# DAC_SET.net
KiCad netlist of a schematic drawn in Altium Designer
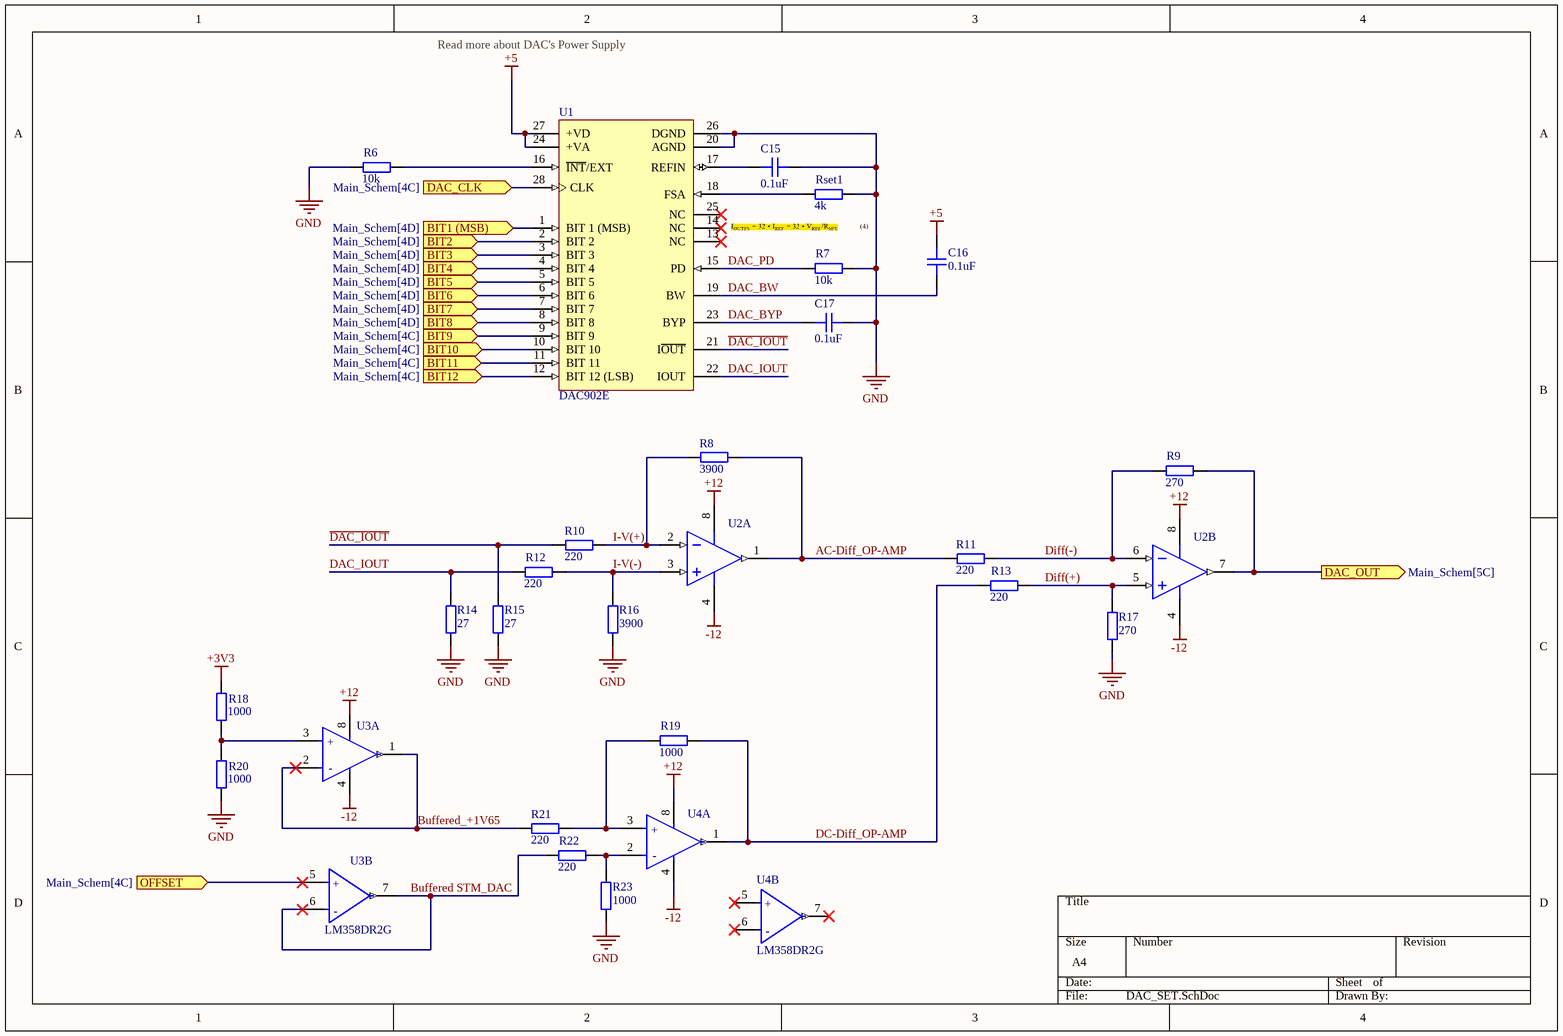
[diagram p0: DAC_SET.SchDoc]

(export (version "E")
  (design (tool "Eeschema 10.0.6"))
  (components
    (comp (ref "C15")
      (value "0.1uF")
      (footprint "CAP_1210")
      (description "Capacitor SMD 1210")
      (libsource (lib "Schematic-Lib-PhilsLab (1)") (part "CAP_1210"))
    )
    (comp (ref "C16")
      (value "0.1uF")
      (footprint "CAP_1210")
      (description "Capacitor SMD 1210")
      (libsource (lib "Schematic-Lib-PhilsLab (1)") (part "CAP_1210"))
    )
    (comp (ref "C17")
      (value "0.1uF")
      (footprint "CAP_1210")
      (description "Capacitor SMD 1210")
      (libsource (lib "Schematic-Lib-PhilsLab (1)") (part "CAP_1210"))
    )
    (comp (ref "R6")
      (value "10k")
      (footprint "RES_0805")
      (description "Resistor SMD 0805")
      (libsource (lib "Schematic-Lib-PhilsLab (1)") (part "RES_0805"))
    )
    (comp (ref "R7")
      (value "10k")
      (footprint "RES_0805")
      (description "Resistor SMD 0805")
      (libsource (lib "Schematic-Lib-PhilsLab (1)") (part "RES_0805"))
    )
    (comp (ref "R8")
      (value "3900")
      (footprint "RES_0805")
      (description "Resistor SMD 0805")
      (libsource (lib "Schematic-Lib-PhilsLab (1)") (part "RES_0805"))
    )
    (comp (ref "R9")
      (value "270")
      (footprint "RES_0805")
      (description "Resistor SMD 0805")
      (libsource (lib "Schematic-Lib-PhilsLab (1)") (part "RES_0805"))
    )
    (comp (ref "R10")
      (value "220")
      (footprint "RES_0805")
      (description "Resistor SMD 0805")
      (libsource (lib "Schematic-Lib-PhilsLab (1)") (part "RES_0805"))
    )
    (comp (ref "R11")
      (value "220")
      (footprint "RES_0805")
      (description "Resistor SMD 0805")
      (libsource (lib "Schematic-Lib-PhilsLab (1)") (part "RES_0805"))
    )
    (comp (ref "R12")
      (value "220")
      (footprint "RES_0805")
      (description "Resistor SMD 0805")
      (libsource (lib "Schematic-Lib-PhilsLab (1)") (part "RES_0805"))
    )
    (comp (ref "R13")
      (value "220")
      (footprint "RES_0805")
      (description "Resistor SMD 0805")
      (libsource (lib "Schematic-Lib-PhilsLab (1)") (part "RES_0805"))
    )
    (comp (ref "R14")
      (value "27")
      (footprint "RES_0805")
      (description "Resistor SMD 0805")
      (libsource (lib "Schematic-Lib-PhilsLab (1)") (part "RES_0805"))
    )
    (comp (ref "R15")
      (value "27")
      (footprint "RES_0805")
      (description "Resistor SMD 0805")
      (libsource (lib "Schematic-Lib-PhilsLab (1)") (part "RES_0805"))
    )
    (comp (ref "R16")
      (value "3900")
      (footprint "RES_0805")
      (description "Resistor SMD 0805")
      (libsource (lib "Schematic-Lib-PhilsLab (1)") (part "RES_0805"))
    )
    (comp (ref "R17")
      (value "270")
      (footprint "RES_0805")
      (description "Resistor SMD 0805")
      (libsource (lib "Schematic-Lib-PhilsLab (1)") (part "RES_0805"))
    )
    (comp (ref "R18")
      (value "1000")
      (footprint "RES_0805")
      (description "Resistor SMD 0805")
      (libsource (lib "Schematic-Lib-PhilsLab (1)") (part "RES_0805"))
    )
    (comp (ref "R19")
      (value "1000")
      (footprint "RES_0805")
      (description "Resistor SMD 0805")
      (libsource (lib "Schematic-Lib-PhilsLab (1)") (part "RES_0805"))
    )
    (comp (ref "R20")
      (value "1000")
      (footprint "RES_0805")
      (description "Resistor SMD 0805")
      (libsource (lib "Schematic-Lib-PhilsLab (1)") (part "RES_0805"))
    )
    (comp (ref "R21")
      (value "220")
      (footprint "RES_0805")
      (description "Resistor SMD 0805")
      (libsource (lib "Schematic-Lib-PhilsLab (1)") (part "RES_0805"))
    )
    (comp (ref "R22")
      (value "220")
      (footprint "RES_0805")
      (description "Resistor SMD 0805")
      (libsource (lib "Schematic-Lib-PhilsLab (1)") (part "RES_0805"))
    )
    (comp (ref "R23")
      (value "1000")
      (footprint "RES_0805")
      (description "Resistor SMD 0805")
      (libsource (lib "Schematic-Lib-PhilsLab (1)") (part "RES_0805"))
    )
    (comp (ref "Rset1")
      (value "4k")
      (footprint "RES_0805")
      (description "Resistor SMD 0805")
      (libsource (lib "Schematic-Lib-PhilsLab (1)") (part "RES_0805"))
    )
    (comp (ref "U1")
      (value "DAC902E")
      (footprint "TI-PW28_L")
      (fields (field (name "MANUFACTURER") "Texas Instruments"))
      (libsource (lib "Altium Content Vault") (part "TI-DAC902-28"))
    )
    (comp (ref "U2")
      (value "AD8066ARZ-R7")
      (footprint "ADI-R-8_M")
      (fields (field (name "MANUFACTURER") "Analog Devices") (field (name "GENERIC PART NUMBER") "AD8066"))
      (libsource (lib "Altium Content Vault") (part "ADI-AD80XX-RX-8"))
    )
    (comp (ref "U3")
      (value "LM358DR2G")
      (footprint "FP-751-07-IPC_C")
      (description "IC OPAMP GP 2 CIRCUIT 8SOIC")
      (libsource (lib "Altium Content Vault") (part "992a6607d1d88c80ee6b45e5ba6cb1b"))
    )
    (comp (ref "U4")
      (value "LM358DR2G")
      (footprint "FP-751-07-IPC_C")
      (description "IC OPAMP GP 2 CIRCUIT 8SOIC")
      (libsource (lib "Altium Content Vault") (part "992a6607d1d88c80ee6b45e5ba6cb1b"))
    )
  )
  (nets
    (net (code "1") (name "+3V3") (class "Default")
      (node (ref "R18") (pin "1") (pinfunction "1_1") (pintype "passive"))
    )
    (net (code "2") (name "+5") (class "Default")
      (node (ref "C16") (pin "2") (pinfunction "2_2") (pintype "passive"))
      (node (ref "U1") (pin "24") (pinfunction "+VA_24") (pintype "power_in"))
      (node (ref "U1") (pin "27") (pinfunction "+VD_27") (pintype "power_in"))
    )
    (net (code "3") (name "+12") (class "Default")
      (node (ref "U2") (pin "8") (pinfunction "+VS_8") (pintype "power_in"))
      (node (ref "U3") (pin "8") (pinfunction "VCC_8") (pintype "power_in"))
      (node (ref "U4") (pin "8") (pinfunction "VCC_8") (pintype "power_in"))
    )
    (net (code "4") (name "-12") (class "Default")
      (node (ref "U2") (pin "4") (pinfunction "-VS_4") (pintype "power_in"))
      (node (ref "U3") (pin "4") (pinfunction "VEE/GND_4") (pintype "power_in"))
      (node (ref "U4") (pin "4") (pinfunction "VEE/GND_4") (pintype "power_in"))
    )
    (net (code "5") (name "/AC-Diff_OP-AMP") (class "Default")
      (node (ref "R11") (pin "2") (pinfunction "2_2") (pintype "passive"))
      (node (ref "R8") (pin "2") (pinfunction "2_2") (pintype "passive"))
      (node (ref "U2") (pin "1") (pinfunction "VOUT_1_1") (pintype "output"))
    )
    (net (code "6") (name "/BIT1 (MSB)") (class "Default")
      (node (ref "U1") (pin "1") (pinfunction "BIT_1_(MSB)_1") (pintype "input"))
    )
    (net (code "7") (name "/BIT2") (class "Default")
      (node (ref "U1") (pin "2") (pinfunction "BIT_2_2") (pintype "input"))
    )
    (net (code "8") (name "/BIT3") (class "Default")
      (node (ref "U1") (pin "3") (pinfunction "BIT_3_3") (pintype "input"))
    )
    (net (code "9") (name "/BIT4") (class "Default")
      (node (ref "U1") (pin "4") (pinfunction "BIT_4_4") (pintype "input"))
    )
    (net (code "10") (name "/BIT5") (class "Default")
      (node (ref "U1") (pin "5") (pinfunction "BIT_5_5") (pintype "input"))
    )
    (net (code "11") (name "/BIT6") (class "Default")
      (node (ref "U1") (pin "6") (pinfunction "BIT_6_6") (pintype "input"))
    )
    (net (code "12") (name "/BIT7") (class "Default")
      (node (ref "U1") (pin "7") (pinfunction "BIT_7_7") (pintype "input"))
    )
    (net (code "13") (name "/BIT8") (class "Default")
      (node (ref "U1") (pin "8") (pinfunction "BIT_8_8") (pintype "input"))
    )
    (net (code "14") (name "/BIT9") (class "Default")
      (node (ref "U1") (pin "9") (pinfunction "BIT_9_9") (pintype "input"))
    )
    (net (code "15") (name "/BIT10") (class "Default")
      (node (ref "U1") (pin "10") (pinfunction "BIT_10_10") (pintype "input"))
    )
    (net (code "16") (name "/BIT11") (class "Default")
      (node (ref "U1") (pin "11") (pinfunction "BIT_11_11") (pintype "input"))
    )
    (net (code "17") (name "/BIT12") (class "Default")
      (node (ref "U1") (pin "12") (pinfunction "BIT_12_(LSB)_12") (pintype "input"))
    )
    (net (code "18") (name "/Buffered STM_DAC") (class "Default")
      (node (ref "R22") (pin "2") (pinfunction "2_2") (pintype "passive"))
      (node (ref "U3") (pin "6") (pinfunction "INPUT_B-_6") (pintype "tri_state"))
      (node (ref "U3") (pin "7") (pinfunction "OUTPUT_B_7") (pintype "output"))
    )
    (net (code "19") (name "/Buffered_+1V65") (class "Default")
      (node (ref "R21") (pin "2") (pinfunction "2_2") (pintype "passive"))
      (node (ref "U3") (pin "1") (pinfunction "OUTPUT_A_1") (pintype "output"))
      (node (ref "U3") (pin "2") (pinfunction "INPUT_A-_2") (pintype "tri_state"))
    )
    (net (code "20") (name "/DAC_BW") (class "Default")
      (node (ref "C16") (pin "1") (pinfunction "1_1") (pintype "passive"))
      (node (ref "U1") (pin "19") (pinfunction "BW_19") (pintype "passive"))
    )
    (net (code "21") (name "/DAC_BYP") (class "Default")
      (node (ref "C17") (pin "1") (pinfunction "1_1") (pintype "passive"))
      (node (ref "U1") (pin "23") (pinfunction "BYP_23") (pintype "passive"))
    )
    (net (code "22") (name "/DAC_CLK") (class "Default")
      (node (ref "U1") (pin "28") (pinfunction "CLK_28") (pintype "input"))
    )
    (net (code "23") (name "/DAC_IOUT") (class "Default")
      (node (ref "R12") (pin "2") (pinfunction "2_2") (pintype "passive"))
      (node (ref "R14") (pin "1") (pinfunction "1_1") (pintype "passive"))
      (node (ref "U1") (pin "22") (pinfunction "IOUT_22") (pintype "tri_state"))
    )
    (net (code "24") (name "/DAC_OUT") (class "Default")
      (node (ref "R9") (pin "1") (pinfunction "1_1") (pintype "passive"))
      (node (ref "U2") (pin "7") (pinfunction "VOUT_2_7") (pintype "output"))
    )
    (net (code "25") (name "/DAC_PD") (class "Default")
      (node (ref "R7") (pin "2") (pinfunction "2_2") (pintype "passive"))
      (node (ref "U1") (pin "15") (pinfunction "PD_15") (pintype "input"))
    )
    (net (code "26") (name "/DC-Diff_OP-AMP") (class "Default")
      (node (ref "R13") (pin "2") (pinfunction "2_2") (pintype "passive"))
      (node (ref "R19") (pin "1") (pinfunction "1_1") (pintype "passive"))
      (node (ref "U4") (pin "1") (pinfunction "OUTPUT_A_1") (pintype "output"))
    )
    (net (code "27") (name "/Diff(+)") (class "Default")
      (node (ref "R13") (pin "1") (pinfunction "1_1") (pintype "passive"))
      (node (ref "R17") (pin "1") (pinfunction "1_1") (pintype "passive"))
      (node (ref "U2") (pin "5") (pinfunction "+IN_2_5") (pintype "input"))
    )
    (net (code "28") (name "/Diff(-)") (class "Default")
      (node (ref "R11") (pin "1") (pinfunction "1_1") (pintype "passive"))
      (node (ref "R9") (pin "2") (pinfunction "2_2") (pintype "passive"))
      (node (ref "U2") (pin "6") (pinfunction "-IN_2_6") (pintype "input"))
    )
    (net (code "29") (name "/I-V(+)") (class "Default")
      (node (ref "R10") (pin "1") (pinfunction "1_1") (pintype "passive"))
      (node (ref "R8") (pin "1") (pinfunction "1_1") (pintype "passive"))
      (node (ref "U2") (pin "2") (pinfunction "-IN_1_2") (pintype "input"))
    )
    (net (code "30") (name "/I-V(-)") (class "Default")
      (node (ref "R12") (pin "1") (pinfunction "1_1") (pintype "passive"))
      (node (ref "R16") (pin "1") (pinfunction "1_1") (pintype "passive"))
      (node (ref "U2") (pin "3") (pinfunction "+IN_1_3") (pintype "input"))
    )
    (net (code "31") (name "/OFFSET") (class "Default")
      (node (ref "U3") (pin "5") (pinfunction "INPUT_B+_5") (pintype "tri_state+no_connect"))
    )
    (net (code "32") (name "/~{DAC_IOUT}") (class "Default")
      (node (ref "R10") (pin "2") (pinfunction "2_2") (pintype "passive"))
      (node (ref "R15") (pin "1") (pinfunction "1_1") (pintype "passive"))
      (node (ref "U1") (pin "21") (pinfunction "I~{OUT}_21") (pintype "tri_state"))
    )
    (net (code "33") (name "GND") (class "Default")
      (node (ref "C15") (pin "2") (pinfunction "2_2") (pintype "passive"))
      (node (ref "C17") (pin "2") (pinfunction "2_2") (pintype "passive"))
      (node (ref "R14") (pin "2") (pinfunction "2_2") (pintype "passive"))
      (node (ref "R15") (pin "2") (pinfunction "2_2") (pintype "passive"))
      (node (ref "R16") (pin "2") (pinfunction "2_2") (pintype "passive"))
      (node (ref "R17") (pin "2") (pinfunction "2_2") (pintype "passive"))
      (node (ref "R20") (pin "2") (pinfunction "2_2") (pintype "passive"))
      (node (ref "R23") (pin "2") (pinfunction "2_2") (pintype "passive"))
      (node (ref "R6") (pin "2") (pinfunction "2_2") (pintype "passive"))
      (node (ref "R7") (pin "1") (pinfunction "1_1") (pintype "passive"))
      (node (ref "Rset1") (pin "1") (pinfunction "1_1") (pintype "passive"))
      (node (ref "U1") (pin "20") (pinfunction "AGND_20") (pintype "power_in"))
      (node (ref "U1") (pin "26") (pinfunction "DGND_26") (pintype "power_in"))
    )
    (net (code "34") (name "Net-(U1-FSA)") (class "Default")
      (node (ref "Rset1") (pin "2") (pinfunction "2_2") (pintype "passive"))
      (node (ref "U1") (pin "18") (pinfunction "FSA_18") (pintype "input"))
    )
    (net (code "35") (name "Net-(U1-REFIN)") (class "Default")
      (node (ref "C15") (pin "1") (pinfunction "1_1") (pintype "passive"))
      (node (ref "U1") (pin "17") (pinfunction "REFIN_17") (pintype "bidirectional"))
    )
    (net (code "36") (name "Net-(U1-~{INT}{slash}EXT)") (class "Default")
      (node (ref "R6") (pin "1") (pinfunction "1_1") (pintype "passive"))
      (node (ref "U1") (pin "16") (pinfunction "~{INT}/EXT_16") (pintype "input"))
    )
    (net (code "37") (name "Net-(U3A-INPUT_A+)") (class "Default")
      (node (ref "R18") (pin "2") (pinfunction "2_2") (pintype "passive"))
      (node (ref "R20") (pin "1") (pinfunction "1_1") (pintype "passive"))
      (node (ref "U3") (pin "3") (pinfunction "INPUT_A+_3") (pintype "tri_state"))
    )
    (net (code "38") (name "Net-(U4A-INPUT_A+)") (class "Default")
      (node (ref "R19") (pin "2") (pinfunction "2_2") (pintype "passive"))
      (node (ref "R21") (pin "1") (pinfunction "1_1") (pintype "passive"))
      (node (ref "U4") (pin "3") (pinfunction "INPUT_A+_3") (pintype "tri_state"))
    )
    (net (code "39") (name "Net-(U4A-INPUT_A-)") (class "Default")
      (node (ref "R22") (pin "1") (pinfunction "1_1") (pintype "passive"))
      (node (ref "R23") (pin "1") (pinfunction "1_1") (pintype "passive"))
      (node (ref "U4") (pin "2") (pinfunction "INPUT_A-_2") (pintype "tri_state"))
    )
    (net (code "40") (name "unconnected-(U1-NC-Pad13)") (class "Default")
      (node (ref "U1") (pin "13") (pinfunction "NC_13") (pintype "passive+no_connect"))
    )
    (net (code "41") (name "unconnected-(U1-NC-Pad14)") (class "Default")
      (node (ref "U1") (pin "14") (pinfunction "NC_14") (pintype "passive+no_connect"))
    )
    (net (code "42") (name "unconnected-(U1-NC-Pad25)") (class "Default")
      (node (ref "U1") (pin "25") (pinfunction "NC_25") (pintype "passive+no_connect"))
    )
    (net (code "43") (name "unconnected-(U4B-INPUT_B+-Pad5)") (class "Default")
      (node (ref "U4") (pin "5") (pinfunction "INPUT_B+_5") (pintype "tri_state+no_connect"))
    )
    (net (code "44") (name "unconnected-(U4B-INPUT_B--Pad6)") (class "Default")
      (node (ref "U4") (pin "6") (pinfunction "INPUT_B-_6") (pintype "tri_state+no_connect"))
    )
    (net (code "45") (name "unconnected-(U4B-OUTPUT_B-Pad7)") (class "Default")
      (node (ref "U4") (pin "7") (pinfunction "OUTPUT_B_7") (pintype "output+no_connect"))
    )
  )
)
